# 7a_-_Controller.net
KiCad netlist of a schematic drawn in Altium Designer
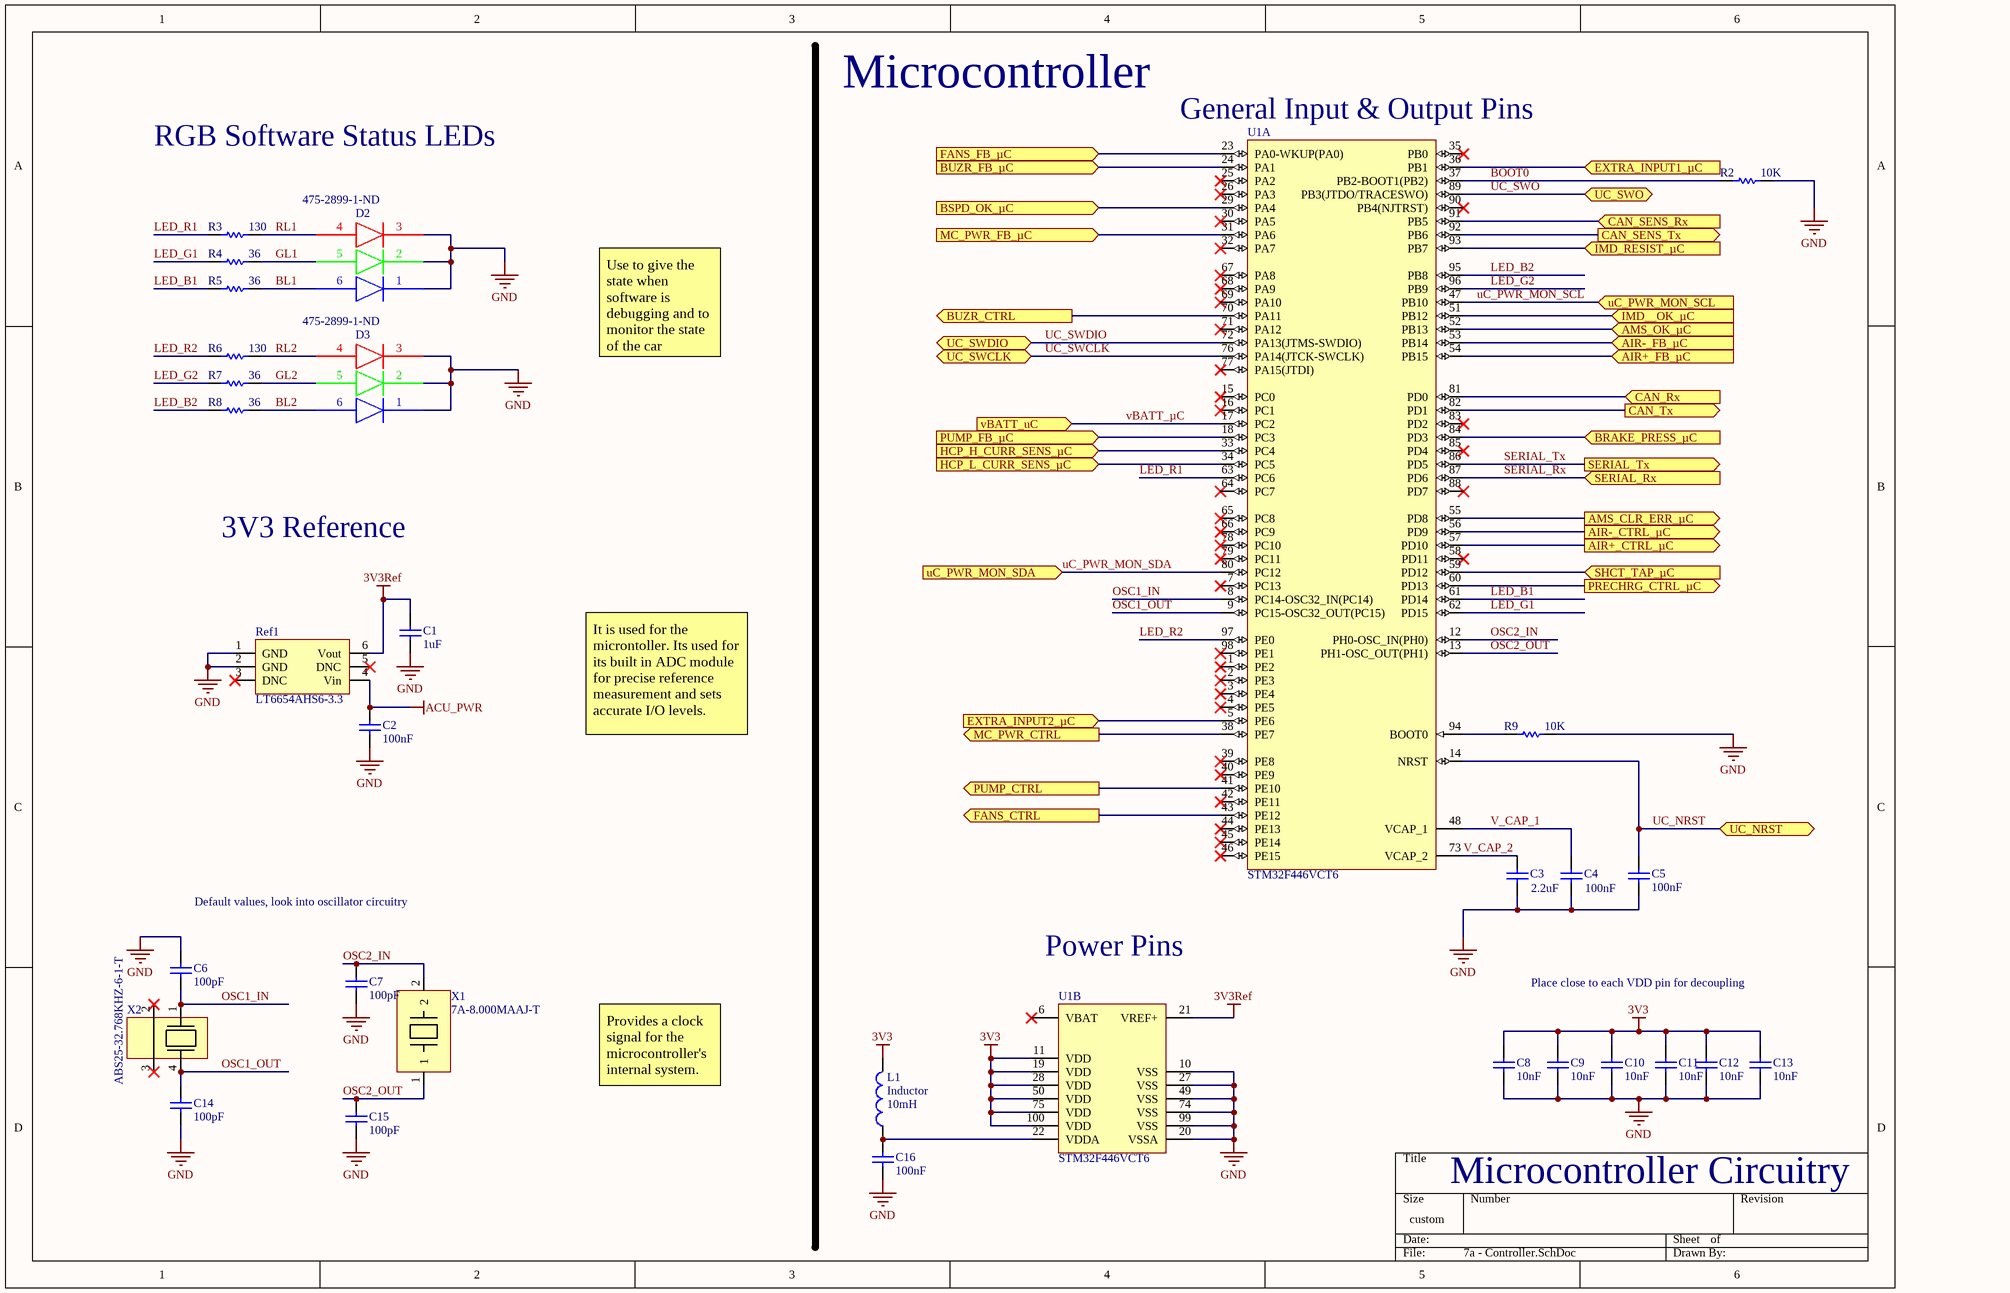
[diagram p0: 7a - Controller.SchDoc]

(export (version "E")
  (design (tool "Eeschema 10.0.6"))
  (components
    (comp (ref "C1")
      (value "1uF")
      (footprint "1608[0603]")
      (description "Capacitor")
      (fields (field (name "Comment") "Cap") (field (name "PUBLISHER") "Altium Limited"))
      (libsource (lib "Miscellaneous Devices") (part "Cap"))
    )
    (comp (ref "C2")
      (value "100nF")
      (footprint "1608[0603]")
      (description "Capacitor")
      (fields (field (name "Comment") "Cap") (field (name "PUBLISHER") "Altium Limited"))
      (libsource (lib "Miscellaneous Devices") (part "Cap"))
    )
    (comp (ref "C3")
      (value "2.2uF")
      (footprint "CAPC0603(1608)100_N")
      (description "CAP 100nF 10V -20% to +80% 0603 (1608 Metric) Thickness 1mm SMD")
      (fields (field (name "TOLERANCE") "-20% to +80%"))
      (libsource (lib "Altium Content Vault") (part "CAP"))
    )
    (comp (ref "C4")
      (value "100nF")
      (footprint "CAPC0603(1608)100_N")
      (description "CAP 100nF 10V -20% to +80% 0603 (1608 Metric) Thickness 1mm SMD")
      (fields (field (name "TOLERANCE") "-20% to +80%"))
      (libsource (lib "Altium Content Vault") (part "CAP"))
    )
    (comp (ref "C5")
      (value "100nF")
      (footprint "1608[0603]")
      (description "Capacitor")
      (fields (field (name "Comment") "Cap") (field (name "PUBLISHER") "Altium Limited"))
      (libsource (lib "Miscellaneous Devices") (part "Cap"))
    )
    (comp (ref "C6")
      (value "100pF")
      (footprint "1608[0603]")
      (description "Capacitor")
      (fields (field (name "Comment") "Cap") (field (name "PUBLISHER") "Altium Limited"))
      (libsource (lib "Miscellaneous Devices") (part "Cap"))
    )
    (comp (ref "C7")
      (value "100pF")
      (footprint "1608[0603]")
      (description "Capacitor")
      (fields (field (name "Comment") "Cap") (field (name "PUBLISHER") "Altium Limited"))
      (libsource (lib "Miscellaneous Devices") (part "Cap"))
    )
    (comp (ref "C8")
      (value "10nF")
      (footprint "1608[0603]")
      (description "Capacitor")
      (fields (field (name "Comment") "Cap") (field (name "PUBLISHER") "Altium Limited"))
      (libsource (lib "Miscellaneous Devices") (part "Cap"))
    )
    (comp (ref "C9")
      (value "10nF")
      (footprint "1608[0603]")
      (description "Capacitor")
      (fields (field (name "Comment") "Cap") (field (name "PUBLISHER") "Altium Limited"))
      (libsource (lib "Miscellaneous Devices") (part "Cap"))
    )
    (comp (ref "C10")
      (value "10nF")
      (footprint "1608[0603]")
      (description "Capacitor")
      (fields (field (name "Comment") "Cap") (field (name "PUBLISHER") "Altium Limited"))
      (libsource (lib "Miscellaneous Devices") (part "Cap"))
    )
    (comp (ref "C11")
      (value "10nF")
      (footprint "1608[0603]")
      (description "Capacitor")
      (fields (field (name "Comment") "Cap") (field (name "PUBLISHER") "Altium Limited"))
      (libsource (lib "Miscellaneous Devices") (part "Cap"))
    )
    (comp (ref "C12")
      (value "10nF")
      (footprint "1608[0603]")
      (description "Capacitor")
      (fields (field (name "Comment") "Cap") (field (name "PUBLISHER") "Altium Limited"))
      (libsource (lib "Miscellaneous Devices") (part "Cap"))
    )
    (comp (ref "C13")
      (value "10nF")
      (footprint "1608[0603]")
      (description "Capacitor")
      (fields (field (name "Comment") "Cap") (field (name "PUBLISHER") "Altium Limited"))
      (libsource (lib "Miscellaneous Devices") (part "Cap"))
    )
    (comp (ref "C14")
      (value "100pF")
      (footprint "1608[0603]")
      (description "Capacitor")
      (fields (field (name "Comment") "Cap") (field (name "PUBLISHER") "Altium Limited"))
      (libsource (lib "Miscellaneous Devices") (part "Cap"))
    )
    (comp (ref "C15")
      (value "100pF")
      (footprint "1608[0603]")
      (description "Capacitor")
      (fields (field (name "Comment") "Cap") (field (name "PUBLISHER") "Altium Limited"))
      (libsource (lib "Miscellaneous Devices") (part "Cap"))
    )
    (comp (ref "C16")
      (value "100nF")
      (footprint "1608[0603]")
      (description "Capacitor")
      (fields (field (name "Comment") "Cap") (field (name "PUBLISHER") "Altium Limited"))
      (libsource (lib "Miscellaneous Devices") (part "Cap"))
    )
    (comp (ref "D2")
      (value "~")
      (footprint "CLX6C-FKB")
      (fields
        (field (name "MANUFACTURER") "Cree Inc.")
        (field (name "MANUFACTURER PART NUMBER") "CLX6C-FKB-CGJKNCFBB789363")
        (field (name "SUPPLIER PART NUMBER 1") "475-2899-1-ND")
      )
      (libsource (lib "VCU Library") (part "LED - CLX6C-FKB-CGJKNCFBB789363 RGB"))
    )
    (comp (ref "D3")
      (value "~")
      (footprint "CLX6C-FKB")
      (fields
        (field (name "MANUFACTURER") "Cree Inc.")
        (field (name "MANUFACTURER PART NUMBER") "CLX6C-FKB-CGJKNCFBB789363")
        (field (name "SUPPLIER PART NUMBER 1") "475-2899-1-ND")
      )
      (libsource (lib "VCU Library") (part "LED - CLX6C-FKB-CGJKNCFBB789363 RGB"))
    )
    (comp (ref "L1")
      (value "Inductor")
      (footprint "0402-A")
      (fields (field (name "ALTIUM_VALUE") "10mH") (field (name "PUBLISHER") "Altium Limited"))
      (libsource (lib "Miscellaneous Devices") (part "Inductor"))
    )
    (comp (ref "R2")
      (value "10K")
      (footprint "1608[0603]")
      (description "Resistor")
      (fields (field (name "Comment") "Res1") (field (name "PUBLISHER") "Altium Limited"))
      (libsource (lib "Miscellaneous Devices") (part "Res1"))
    )
    (comp (ref "R3")
      (value "130")
      (footprint "1608[0603]")
      (description "Resistor")
      (fields (field (name "Comment") "Res1") (field (name "PUBLISHER") "Altium Limited"))
      (libsource (lib "Miscellaneous Devices") (part "Res1"))
    )
    (comp (ref "R4")
      (value "36")
      (footprint "1608[0603]")
      (description "Resistor")
      (fields (field (name "Comment") "Res1") (field (name "PUBLISHER") "Altium Limited"))
      (libsource (lib "Miscellaneous Devices") (part "Res1"))
    )
    (comp (ref "R5")
      (value "36")
      (footprint "1608[0603]")
      (description "Resistor")
      (fields (field (name "Comment") "Res1") (field (name "PUBLISHER") "Altium Limited"))
      (libsource (lib "Miscellaneous Devices") (part "Res1"))
    )
    (comp (ref "R6")
      (value "130")
      (footprint "1608[0603]")
      (description "Resistor")
      (fields (field (name "Comment") "Res1") (field (name "PUBLISHER") "Altium Limited"))
      (libsource (lib "Miscellaneous Devices") (part "Res1"))
    )
    (comp (ref "R7")
      (value "36")
      (footprint "1608[0603]")
      (description "Resistor")
      (fields (field (name "Comment") "Res1") (field (name "PUBLISHER") "Altium Limited"))
      (libsource (lib "Miscellaneous Devices") (part "Res1"))
    )
    (comp (ref "R8")
      (value "36")
      (footprint "1608[0603]")
      (description "Resistor")
      (fields (field (name "Comment") "Res1") (field (name "PUBLISHER") "Altium Limited"))
      (libsource (lib "Miscellaneous Devices") (part "Res1"))
    )
    (comp (ref "R9")
      (value "10K")
      (footprint "1608[0603]")
      (description "Resistor")
      (fields (field (name "Comment") "Res1") (field (name "PUBLISHER") "Altium Limited"))
      (libsource (lib "Miscellaneous Devices") (part "Res1"))
    )
    (comp (ref "Ref1")
      (value "LT6654AHS6-3.3")
      (footprint "TSOT-23")
      (description "TSOT-23-56")
      (fields
        (field (name "DIGIKEY PART NUMBER") "LT6654AHS6-3.3#TRMPBFCT-ND")
        (field (name "MANUFACTURER") "Linear Technology")
      )
      (libsource (lib "VCU Library") (part "LT6654AHS6-3.3"))
    )
    (comp (ref "U1")
      (value "STM32F446VCT6")
      (footprint "STM-LQFP100_L")
      (libsource (lib "Altium Content Vault") (part "MC-ARM-STM32F446-LQFP100"))
    )
    (comp (ref "X1")
      (value "7A-8.000MAAJ-T")
      (footprint "5 x 3.2 mm SMD")
      (fields (field (name "MANUFACTURER") "TXC CORPORATION"))
      (libsource (lib "VCU Library") (part "8MHz crystal, 7A-8.000MAAJ-T"))
    )
    (comp (ref "X2")
      (value "ABS25-32.768KHZ-6-1-T")
      (footprint "SOJ-4, 5.5mm Pitch")
      (fields
        (field (name "DIGIKEY PART NUMBER") "535-10241-1-ND")
        (field (name "MANUFACTURER") "Abracon LLC")
      )
      (libsource (lib "VCU Library") (part "ABS25-32.768KHZ-6-1-T"))
    )
  )
  (nets
    (net (code "1") (name "/AIR+_CTRL_µC") (class "Default")
      (node (ref "U1") (pin "57") (pinfunction "PD10_57") (pintype "bidirectional"))
    )
    (net (code "2") (name "/AIR+_FB_µC") (class "Default")
      (node (ref "U1") (pin "54") (pinfunction "PB15_54") (pintype "bidirectional"))
    )
    (net (code "3") (name "/AIR-_CTRL_µC") (class "Default")
      (node (ref "U1") (pin "56") (pinfunction "PD9_56") (pintype "bidirectional"))
    )
    (net (code "4") (name "/AIR-_FB_µC") (class "Default")
      (node (ref "U1") (pin "53") (pinfunction "PB14_53") (pintype "bidirectional"))
    )
    (net (code "5") (name "/AMS_CLR_ERR_µC") (class "Default")
      (node (ref "U1") (pin "55") (pinfunction "PD8_55") (pintype "bidirectional"))
    )
    (net (code "6") (name "/AMS_OK_µC") (class "Default")
      (node (ref "U1") (pin "52") (pinfunction "PB13_52") (pintype "bidirectional"))
    )
    (net (code "7") (name "/BL1") (class "Default")
      (node (ref "D2") (pin "6") (pinfunction "B_6") (pintype "passive"))
      (node (ref "R5") (pin "2") (pinfunction "2_2") (pintype "passive"))
    )
    (net (code "8") (name "/BL2") (class "Default")
      (node (ref "D3") (pin "6") (pinfunction "B_6") (pintype "passive"))
      (node (ref "R8") (pin "2") (pinfunction "2_2") (pintype "passive"))
    )
    (net (code "9") (name "/BOOT0") (class "Default")
      (node (ref "R2") (pin "1") (pinfunction "1_1") (pintype "passive"))
      (node (ref "U1") (pin "37") (pinfunction "PB2-BOOT1(PB2)_37") (pintype "bidirectional"))
    )
    (net (code "10") (name "/BRAKE_PRESS_µC") (class "Default")
      (node (ref "U1") (pin "84") (pinfunction "PD3_84") (pintype "bidirectional"))
    )
    (net (code "11") (name "/BSPD_OK_µC") (class "Default")
      (node (ref "U1") (pin "29") (pinfunction "PA4_29") (pintype "bidirectional"))
    )
    (net (code "12") (name "/BUZR_CTRL") (class "Default")
      (node (ref "U1") (pin "70") (pinfunction "PA11_70") (pintype "bidirectional"))
    )
    (net (code "13") (name "/BUZR_FB_µC") (class "Default")
      (node (ref "U1") (pin "24") (pinfunction "PA1_24") (pintype "bidirectional"))
    )
    (net (code "14") (name "/CAN_Rx") (class "Default")
      (node (ref "U1") (pin "81") (pinfunction "PD0_81") (pintype "bidirectional"))
    )
    (net (code "15") (name "/CAN_SENS_Rx") (class "Default")
      (node (ref "U1") (pin "91") (pinfunction "PB5_91") (pintype "bidirectional"))
    )
    (net (code "16") (name "/CAN_SENS_Tx") (class "Default")
      (node (ref "U1") (pin "92") (pinfunction "PB6_92") (pintype "bidirectional"))
    )
    (net (code "17") (name "/CAN_Tx") (class "Default")
      (node (ref "U1") (pin "82") (pinfunction "PD1_82") (pintype "bidirectional"))
    )
    (net (code "18") (name "/EXTRA_INPUT1_µC") (class "Default")
      (node (ref "U1") (pin "36") (pinfunction "PB1_36") (pintype "bidirectional"))
    )
    (net (code "19") (name "/EXTRA_INPUT2_µC") (class "Default")
      (node (ref "U1") (pin "5") (pinfunction "PE6_5") (pintype "bidirectional"))
    )
    (net (code "20") (name "/FANS_CTRL") (class "Default")
      (node (ref "U1") (pin "43") (pinfunction "PE12_43") (pintype "bidirectional"))
    )
    (net (code "21") (name "/FANS_FB_µC") (class "Default")
      (node (ref "U1") (pin "23") (pinfunction "PA0-WKUP(PA0)_23") (pintype "bidirectional"))
    )
    (net (code "22") (name "/GL1") (class "Default")
      (node (ref "D2") (pin "5") (pinfunction "G_5") (pintype "passive"))
      (node (ref "R4") (pin "2") (pinfunction "2_2") (pintype "passive"))
    )
    (net (code "23") (name "/GL2") (class "Default")
      (node (ref "D3") (pin "5") (pinfunction "G_5") (pintype "passive"))
      (node (ref "R7") (pin "2") (pinfunction "2_2") (pintype "passive"))
    )
    (net (code "24") (name "/HCP_H_CURR_SENS_µC") (class "Default")
      (node (ref "U1") (pin "33") (pinfunction "PC4_33") (pintype "bidirectional"))
    )
    (net (code "25") (name "/HCP_L_CURR_SENS_µC") (class "Default")
      (node (ref "U1") (pin "34") (pinfunction "PC5_34") (pintype "bidirectional"))
    )
    (net (code "26") (name "/IMD_RESIST_µC") (class "Default")
      (node (ref "U1") (pin "93") (pinfunction "PB7_93") (pintype "bidirectional"))
    )
    (net (code "27") (name "/IMD__OK_µC") (class "Default")
      (node (ref "U1") (pin "51") (pinfunction "PB12_51") (pintype "bidirectional"))
    )
    (net (code "28") (name "/LED_B1") (class "Default")
      (node (ref "R5") (pin "1") (pinfunction "1_1") (pintype "passive"))
      (node (ref "U1") (pin "61") (pinfunction "PD14_61") (pintype "bidirectional"))
    )
    (net (code "29") (name "/LED_B2") (class "Default")
      (node (ref "R8") (pin "1") (pinfunction "1_1") (pintype "passive"))
      (node (ref "U1") (pin "95") (pinfunction "PB8_95") (pintype "bidirectional"))
    )
    (net (code "30") (name "/LED_G1") (class "Default")
      (node (ref "R4") (pin "1") (pinfunction "1_1") (pintype "passive"))
      (node (ref "U1") (pin "62") (pinfunction "PD15_62") (pintype "bidirectional"))
    )
    (net (code "31") (name "/LED_G2") (class "Default")
      (node (ref "R7") (pin "1") (pinfunction "1_1") (pintype "passive"))
      (node (ref "U1") (pin "96") (pinfunction "PB9_96") (pintype "bidirectional"))
    )
    (net (code "32") (name "/LED_R1") (class "Default")
      (node (ref "R3") (pin "1") (pinfunction "1_1") (pintype "passive"))
      (node (ref "U1") (pin "63") (pinfunction "PC6_63") (pintype "bidirectional"))
    )
    (net (code "33") (name "/LED_R2") (class "Default")
      (node (ref "R6") (pin "1") (pinfunction "1_1") (pintype "passive"))
      (node (ref "U1") (pin "97") (pinfunction "PE0_97") (pintype "bidirectional"))
    )
    (net (code "34") (name "/MC_PWR_CTRL") (class "Default")
      (node (ref "U1") (pin "38") (pinfunction "PE7_38") (pintype "bidirectional"))
    )
    (net (code "35") (name "/MC_PWR_FB_µC") (class "Default")
      (node (ref "U1") (pin "31") (pinfunction "PA6_31") (pintype "bidirectional"))
    )
    (net (code "36") (name "/OSC1_IN") (class "Default")
      (node (ref "C6") (pin "1") (pinfunction "1_1") (pintype "passive"))
      (node (ref "U1") (pin "8") (pinfunction "PC14-OSC32_IN(PC14)_8") (pintype "bidirectional"))
      (node (ref "X2") (pin "1") (pinfunction "1_1") (pintype "passive"))
    )
    (net (code "37") (name "/OSC1_OUT") (class "Default")
      (node (ref "C14") (pin "2") (pinfunction "2_2") (pintype "passive"))
      (node (ref "U1") (pin "9") (pinfunction "PC15-OSC32_OUT(PC15)_9") (pintype "bidirectional"))
      (node (ref "X2") (pin "4") (pinfunction "4_4") (pintype "passive"))
    )
    (net (code "38") (name "/OSC2_IN") (class "Default")
      (node (ref "C7") (pin "2") (pinfunction "2_2") (pintype "passive"))
      (node (ref "U1") (pin "12") (pinfunction "PH0-OSC_IN(PH0)_12") (pintype "bidirectional"))
      (node (ref "X1") (pin "2") (pinfunction "2_2") (pintype "passive"))
    )
    (net (code "39") (name "/OSC2_OUT") (class "Default")
      (node (ref "C15") (pin "2") (pinfunction "2_2") (pintype "passive"))
      (node (ref "U1") (pin "13") (pinfunction "PH1-OSC_OUT(PH1)_13") (pintype "bidirectional"))
      (node (ref "X1") (pin "1") (pinfunction "1_1") (pintype "passive"))
    )
    (net (code "40") (name "/PRECHRG_CTRL_µC") (class "Default")
      (node (ref "U1") (pin "60") (pinfunction "PD13_60") (pintype "bidirectional"))
    )
    (net (code "41") (name "/PUMP_CTRL") (class "Default")
      (node (ref "U1") (pin "41") (pinfunction "PE10_41") (pintype "bidirectional"))
    )
    (net (code "42") (name "/PUMP_FB_µC") (class "Default")
      (node (ref "U1") (pin "18") (pinfunction "PC3_18") (pintype "bidirectional"))
    )
    (net (code "43") (name "/RL1") (class "Default")
      (node (ref "D2") (pin "4") (pinfunction "R_4") (pintype "passive"))
      (node (ref "R3") (pin "2") (pinfunction "2_2") (pintype "passive"))
    )
    (net (code "44") (name "/RL2") (class "Default")
      (node (ref "D3") (pin "4") (pinfunction "R_4") (pintype "passive"))
      (node (ref "R6") (pin "2") (pinfunction "2_2") (pintype "passive"))
    )
    (net (code "45") (name "/SERIAL_Rx") (class "Default")
      (node (ref "U1") (pin "87") (pinfunction "PD6_87") (pintype "bidirectional"))
    )
    (net (code "46") (name "/SERIAL_Tx") (class "Default")
      (node (ref "U1") (pin "86") (pinfunction "PD5_86") (pintype "bidirectional"))
    )
    (net (code "47") (name "/SHCT_TAP_µC") (class "Default")
      (node (ref "U1") (pin "59") (pinfunction "PD12_59") (pintype "bidirectional"))
    )
    (net (code "48") (name "/UC_NRST") (class "Default")
      (node (ref "C5") (pin "2") (pinfunction "2_2") (pintype "passive"))
      (node (ref "U1") (pin "14") (pinfunction "NRST_14") (pintype "bidirectional"))
    )
    (net (code "49") (name "/UC_SWCLK") (class "Default")
      (node (ref "U1") (pin "76") (pinfunction "PA14(JTCK-SWCLK)_76") (pintype "bidirectional"))
    )
    (net (code "50") (name "/UC_SWDIO") (class "Default")
      (node (ref "U1") (pin "72") (pinfunction "PA13(JTMS-SWDIO)_72") (pintype "bidirectional"))
    )
    (net (code "51") (name "/UC_SWO") (class "Default")
      (node (ref "U1") (pin "89") (pinfunction "PB3(JTDO/TRACESWO)_89") (pintype "bidirectional"))
    )
    (net (code "52") (name "/V_CAP_1") (class "Default")
      (node (ref "C4") (pin "2") (pinfunction "2_2") (pintype "passive"))
      (node (ref "U1") (pin "48") (pinfunction "VCAP_1_48") (pintype "passive"))
    )
    (net (code "53") (name "/V_CAP_2") (class "Default")
      (node (ref "C3") (pin "2") (pinfunction "2_2") (pintype "passive"))
      (node (ref "U1") (pin "73") (pinfunction "VCAP_2_73") (pintype "passive"))
    )
    (net (code "54") (name "/uC_PWR_MON_SCL") (class "Default")
      (node (ref "U1") (pin "47") (pinfunction "PB10_47") (pintype "bidirectional"))
    )
    (net (code "55") (name "/uC_PWR_MON_SDA") (class "Default")
      (node (ref "U1") (pin "80") (pinfunction "PC12_80") (pintype "bidirectional"))
    )
    (net (code "56") (name "/vBATT_µC") (class "Default")
      (node (ref "U1") (pin "17") (pinfunction "PC2_17") (pintype "bidirectional"))
    )
    (net (code "57") (name "3V3") (class "Default")
      (node (ref "C10") (pin "2") (pinfunction "2_2") (pintype "passive"))
      (node (ref "C11") (pin "2") (pinfunction "2_2") (pintype "passive"))
      (node (ref "C12") (pin "2") (pinfunction "2_2") (pintype "passive"))
      (node (ref "C13") (pin "2") (pinfunction "2_2") (pintype "passive"))
      (node (ref "C8") (pin "2") (pinfunction "2_2") (pintype "passive"))
      (node (ref "C9") (pin "2") (pinfunction "2_2") (pintype "passive"))
      (node (ref "L1") (pin "2") (pinfunction "2_2") (pintype "passive"))
      (node (ref "U1") (pin "100") (pinfunction "VDD_100") (pintype "power_in"))
      (node (ref "U1") (pin "11") (pinfunction "VDD_11") (pintype "power_in"))
      (node (ref "U1") (pin "19") (pinfunction "VDD_19") (pintype "power_in"))
      (node (ref "U1") (pin "28") (pinfunction "VDD_28") (pintype "power_in"))
      (node (ref "U1") (pin "50") (pinfunction "VDD_50") (pintype "power_in"))
      (node (ref "U1") (pin "75") (pinfunction "VDD_75") (pintype "power_in"))
    )
    (net (code "58") (name "3V3Ref") (class "Default")
      (node (ref "C1") (pin "2") (pinfunction "2_2") (pintype "passive"))
      (node (ref "Ref1") (pin "6") (pinfunction "Vout_6") (pintype "passive"))
      (node (ref "U1") (pin "21") (pinfunction "VREF+_21") (pintype "power_in"))
    )
    (net (code "59") (name "ACU_PWR") (class "Default")
      (node (ref "C2") (pin "2") (pinfunction "2_2") (pintype "passive"))
      (node (ref "Ref1") (pin "4") (pinfunction "Vin_4") (pintype "passive"))
    )
    (net (code "60") (name "GND") (class "Default")
      (node (ref "C1") (pin "1") (pinfunction "1_1") (pintype "passive"))
      (node (ref "C10") (pin "1") (pinfunction "1_1") (pintype "passive"))
      (node (ref "C11") (pin "1") (pinfunction "1_1") (pintype "passive"))
      (node (ref "C12") (pin "1") (pinfunction "1_1") (pintype "passive"))
      (node (ref "C13") (pin "1") (pinfunction "1_1") (pintype "passive"))
      (node (ref "C14") (pin "1") (pinfunction "1_1") (pintype "passive"))
      (node (ref "C15") (pin "1") (pinfunction "1_1") (pintype "passive"))
      (node (ref "C16") (pin "1") (pinfunction "1_1") (pintype "passive"))
      (node (ref "C2") (pin "1") (pinfunction "1_1") (pintype "passive"))
      (node (ref "C3") (pin "1") (pinfunction "1_1") (pintype "passive"))
      (node (ref "C4") (pin "1") (pinfunction "1_1") (pintype "passive"))
      (node (ref "C5") (pin "1") (pinfunction "1_1") (pintype "passive"))
      (node (ref "C6") (pin "2") (pinfunction "2_2") (pintype "passive"))
      (node (ref "C7") (pin "1") (pinfunction "1_1") (pintype "passive"))
      (node (ref "C8") (pin "1") (pinfunction "1_1") (pintype "passive"))
      (node (ref "C9") (pin "1") (pinfunction "1_1") (pintype "passive"))
      (node (ref "D2") (pin "1") (pinfunction "B_1") (pintype "passive"))
      (node (ref "D2") (pin "2") (pinfunction "G_2") (pintype "passive"))
      (node (ref "D2") (pin "3") (pinfunction "R_3") (pintype "passive"))
      (node (ref "D3") (pin "1") (pinfunction "B_1") (pintype "passive"))
      (node (ref "D3") (pin "2") (pinfunction "G_2") (pintype "passive"))
      (node (ref "D3") (pin "3") (pinfunction "R_3") (pintype "passive"))
      (node (ref "R2") (pin "2") (pinfunction "2_2") (pintype "passive"))
      (node (ref "R9") (pin "2") (pinfunction "2_2") (pintype "passive"))
      (node (ref "Ref1") (pin "1") (pinfunction "GND_1") (pintype "passive"))
      (node (ref "Ref1") (pin "2") (pinfunction "GND_2") (pintype "passive"))
      (node (ref "U1") (pin "10") (pinfunction "VSS_10") (pintype "power_in"))
      (node (ref "U1") (pin "20") (pinfunction "VSSA_20") (pintype "power_in"))
      (node (ref "U1") (pin "27") (pinfunction "VSS_27") (pintype "power_in"))
      (node (ref "U1") (pin "49") (pinfunction "VSS_49") (pintype "power_in"))
      (node (ref "U1") (pin "74") (pinfunction "VSS_74") (pintype "power_in"))
      (node (ref "U1") (pin "99") (pinfunction "VSS_99") (pintype "power_in"))
    )
    (net (code "61") (name "Net-(U1A-BOOT0)") (class "Default")
      (node (ref "R9") (pin "1") (pinfunction "1_1") (pintype "passive"))
      (node (ref "U1") (pin "94") (pinfunction "BOOT0_94") (pintype "input"))
    )
    (net (code "62") (name "Net-(U1B-VDDA)") (class "Default")
      (node (ref "C16") (pin "2") (pinfunction "2_2") (pintype "passive"))
      (node (ref "L1") (pin "1") (pinfunction "1_1") (pintype "passive"))
      (node (ref "U1") (pin "22") (pinfunction "VDDA_22") (pintype "power_in"))
    )
    (net (code "63") (name "unconnected-(Ref1-DNC-Pad3)") (class "Default")
      (node (ref "Ref1") (pin "3") (pinfunction "DNC_3") (pintype "passive+no_connect"))
    )
    (net (code "64") (name "unconnected-(Ref1-DNC-Pad5)") (class "Default")
      (node (ref "Ref1") (pin "5") (pinfunction "DNC_5") (pintype "passive+no_connect"))
    )
    (net (code "65") (name "unconnected-(U1A-PA2-Pad25)") (class "Default")
      (node (ref "U1") (pin "25") (pinfunction "PA2_25") (pintype "bidirectional+no_connect"))
    )
    (net (code "66") (name "unconnected-(U1A-PA3-Pad26)") (class "Default")
      (node (ref "U1") (pin "26") (pinfunction "PA3_26") (pintype "bidirectional+no_connect"))
    )
    (net (code "67") (name "unconnected-(U1A-PA5-Pad30)") (class "Default")
      (node (ref "U1") (pin "30") (pinfunction "PA5_30") (pintype "bidirectional+no_connect"))
    )
    (net (code "68") (name "unconnected-(U1A-PA7-Pad32)") (class "Default")
      (node (ref "U1") (pin "32") (pinfunction "PA7_32") (pintype "bidirectional+no_connect"))
    )
    (net (code "69") (name "unconnected-(U1A-PA8-Pad67)") (class "Default")
      (node (ref "U1") (pin "67") (pinfunction "PA8_67") (pintype "bidirectional+no_connect"))
    )
    (net (code "70") (name "unconnected-(U1A-PA9-Pad68)") (class "Default")
      (node (ref "U1") (pin "68") (pinfunction "PA9_68") (pintype "bidirectional+no_connect"))
    )
    (net (code "71") (name "unconnected-(U1A-PA10-Pad69)") (class "Default")
      (node (ref "U1") (pin "69") (pinfunction "PA10_69") (pintype "bidirectional+no_connect"))
    )
    (net (code "72") (name "unconnected-(U1A-PA12-Pad71)") (class "Default")
      (node (ref "U1") (pin "71") (pinfunction "PA12_71") (pintype "bidirectional+no_connect"))
    )
    (net (code "73") (name "unconnected-(U1A-PA15(JTDI)-Pad77)") (class "Default")
      (node (ref "U1") (pin "77") (pinfunction "PA15(JTDI)_77") (pintype "bidirectional+no_connect"))
    )
    (net (code "74") (name "unconnected-(U1A-PB0-Pad35)") (class "Default")
      (node (ref "U1") (pin "35") (pinfunction "PB0_35") (pintype "bidirectional+no_connect"))
    )
    (net (code "75") (name "unconnected-(U1A-PB4(NJTRST)-Pad90)") (class "Default")
      (node (ref "U1") (pin "90") (pinfunction "PB4(NJTRST)_90") (pintype "bidirectional+no_connect"))
    )
    (net (code "76") (name "unconnected-(U1A-PC0-Pad15)") (class "Default")
      (node (ref "U1") (pin "15") (pinfunction "PC0_15") (pintype "bidirectional+no_connect"))
    )
    (net (code "77") (name "unconnected-(U1A-PC1-Pad16)") (class "Default")
      (node (ref "U1") (pin "16") (pinfunction "PC1_16") (pintype "bidirectional+no_connect"))
    )
    (net (code "78") (name "unconnected-(U1A-PC7-Pad64)") (class "Default")
      (node (ref "U1") (pin "64") (pinfunction "PC7_64") (pintype "bidirectional+no_connect"))
    )
    (net (code "79") (name "unconnected-(U1A-PC8-Pad65)") (class "Default")
      (node (ref "U1") (pin "65") (pinfunction "PC8_65") (pintype "bidirectional+no_connect"))
    )
    (net (code "80") (name "unconnected-(U1A-PC9-Pad66)") (class "Default")
      (node (ref "U1") (pin "66") (pinfunction "PC9_66") (pintype "bidirectional+no_connect"))
    )
    (net (code "81") (name "unconnected-(U1A-PC10-Pad78)") (class "Default")
      (node (ref "U1") (pin "78") (pinfunction "PC10_78") (pintype "bidirectional+no_connect"))
    )
    (net (code "82") (name "unconnected-(U1A-PC11-Pad79)") (class "Default")
      (node (ref "U1") (pin "79") (pinfunction "PC11_79") (pintype "bidirectional+no_connect"))
    )
    (net (code "83") (name "unconnected-(U1A-PC13-Pad7)") (class "Default")
      (node (ref "U1") (pin "7") (pinfunction "PC13_7") (pintype "bidirectional+no_connect"))
    )
    (net (code "84") (name "unconnected-(U1A-PD2-Pad83)") (class "Default")
      (node (ref "U1") (pin "83") (pinfunction "PD2_83") (pintype "bidirectional+no_connect"))
    )
    (net (code "85") (name "unconnected-(U1A-PD4-Pad85)") (class "Default")
      (node (ref "U1") (pin "85") (pinfunction "PD4_85") (pintype "bidirectional+no_connect"))
    )
    (net (code "86") (name "unconnected-(U1A-PD7-Pad88)") (class "Default")
      (node (ref "U1") (pin "88") (pinfunction "PD7_88") (pintype "bidirectional+no_connect"))
    )
    (net (code "87") (name "unconnected-(U1A-PD11-Pad58)") (class "Default")
      (node (ref "U1") (pin "58") (pinfunction "PD11_58") (pintype "bidirectional+no_connect"))
    )
    (net (code "88") (name "unconnected-(U1A-PE1-Pad98)") (class "Default")
      (node (ref "U1") (pin "98") (pinfunction "PE1_98") (pintype "bidirectional+no_connect"))
    )
    (net (code "89") (name "unconnected-(U1A-PE2-Pad1)") (class "Default")
      (node (ref "U1") (pin "1") (pinfunction "PE2_1") (pintype "bidirectional+no_connect"))
    )
    (net (code "90") (name "unconnected-(U1A-PE3-Pad2)") (class "Default")
      (node (ref "U1") (pin "2") (pinfunction "PE3_2") (pintype "bidirectional+no_connect"))
    )
    (net (code "91") (name "unconnected-(U1A-PE4-Pad3)") (class "Default")
      (node (ref "U1") (pin "3") (pinfunction "PE4_3") (pintype "bidirectional+no_connect"))
    )
    (net (code "92") (name "unconnected-(U1A-PE5-Pad4)") (class "Default")
      (node (ref "U1") (pin "4") (pinfunction "PE5_4") (pintype "bidirectional+no_connect"))
    )
    (net (code "93") (name "unconnected-(U1A-PE8-Pad39)") (class "Default")
      (node (ref "U1") (pin "39") (pinfunction "PE8_39") (pintype "bidirectional+no_connect"))
    )
    (net (code "94") (name "unconnected-(U1A-PE9-Pad40)") (class "Default")
      (node (ref "U1") (pin "40") (pinfunction "PE9_40") (pintype "bidirectional+no_connect"))
    )
    (net (code "95") (name "unconnected-(U1A-PE11-Pad42)") (class "Default")
      (node (ref "U1") (pin "42") (pinfunction "PE11_42") (pintype "bidirectional+no_connect"))
    )
    (net (code "96") (name "unconnected-(U1A-PE13-Pad44)") (class "Default")
      (node (ref "U1") (pin "44") (pinfunction "PE13_44") (pintype "bidirectional+no_connect"))
    )
    (net (code "97") (name "unconnected-(U1A-PE14-Pad45)") (class "Default")
      (node (ref "U1") (pin "45") (pinfunction "PE14_45") (pintype "bidirectional+no_connect"))
    )
    (net (code "98") (name "unconnected-(U1A-PE15-Pad46)") (class "Default")
      (node (ref "U1") (pin "46") (pinfunction "PE15_46") (pintype "bidirectional+no_connect"))
    )
    (net (code "99") (name "unconnected-(U1B-VBAT-Pad6)") (class "Default")
      (node (ref "U1") (pin "6") (pinfunction "VBAT_6") (pintype "power_in+no_connect"))
    )
    (net (code "100") (name "unconnected-(X2-Pad2)") (class "Default")
      (node (ref "X2") (pin "2") (pinfunction "2_2") (pintype "passive+no_connect"))
    )
    (net (code "101") (name "unconnected-(X2-Pad3)") (class "Default")
      (node (ref "X2") (pin "3") (pinfunction "3_3") (pintype "passive+no_connect"))
    )
  )
)
